# fejleszt.net
KiCad netlist of a schematic drawn in EAGLE
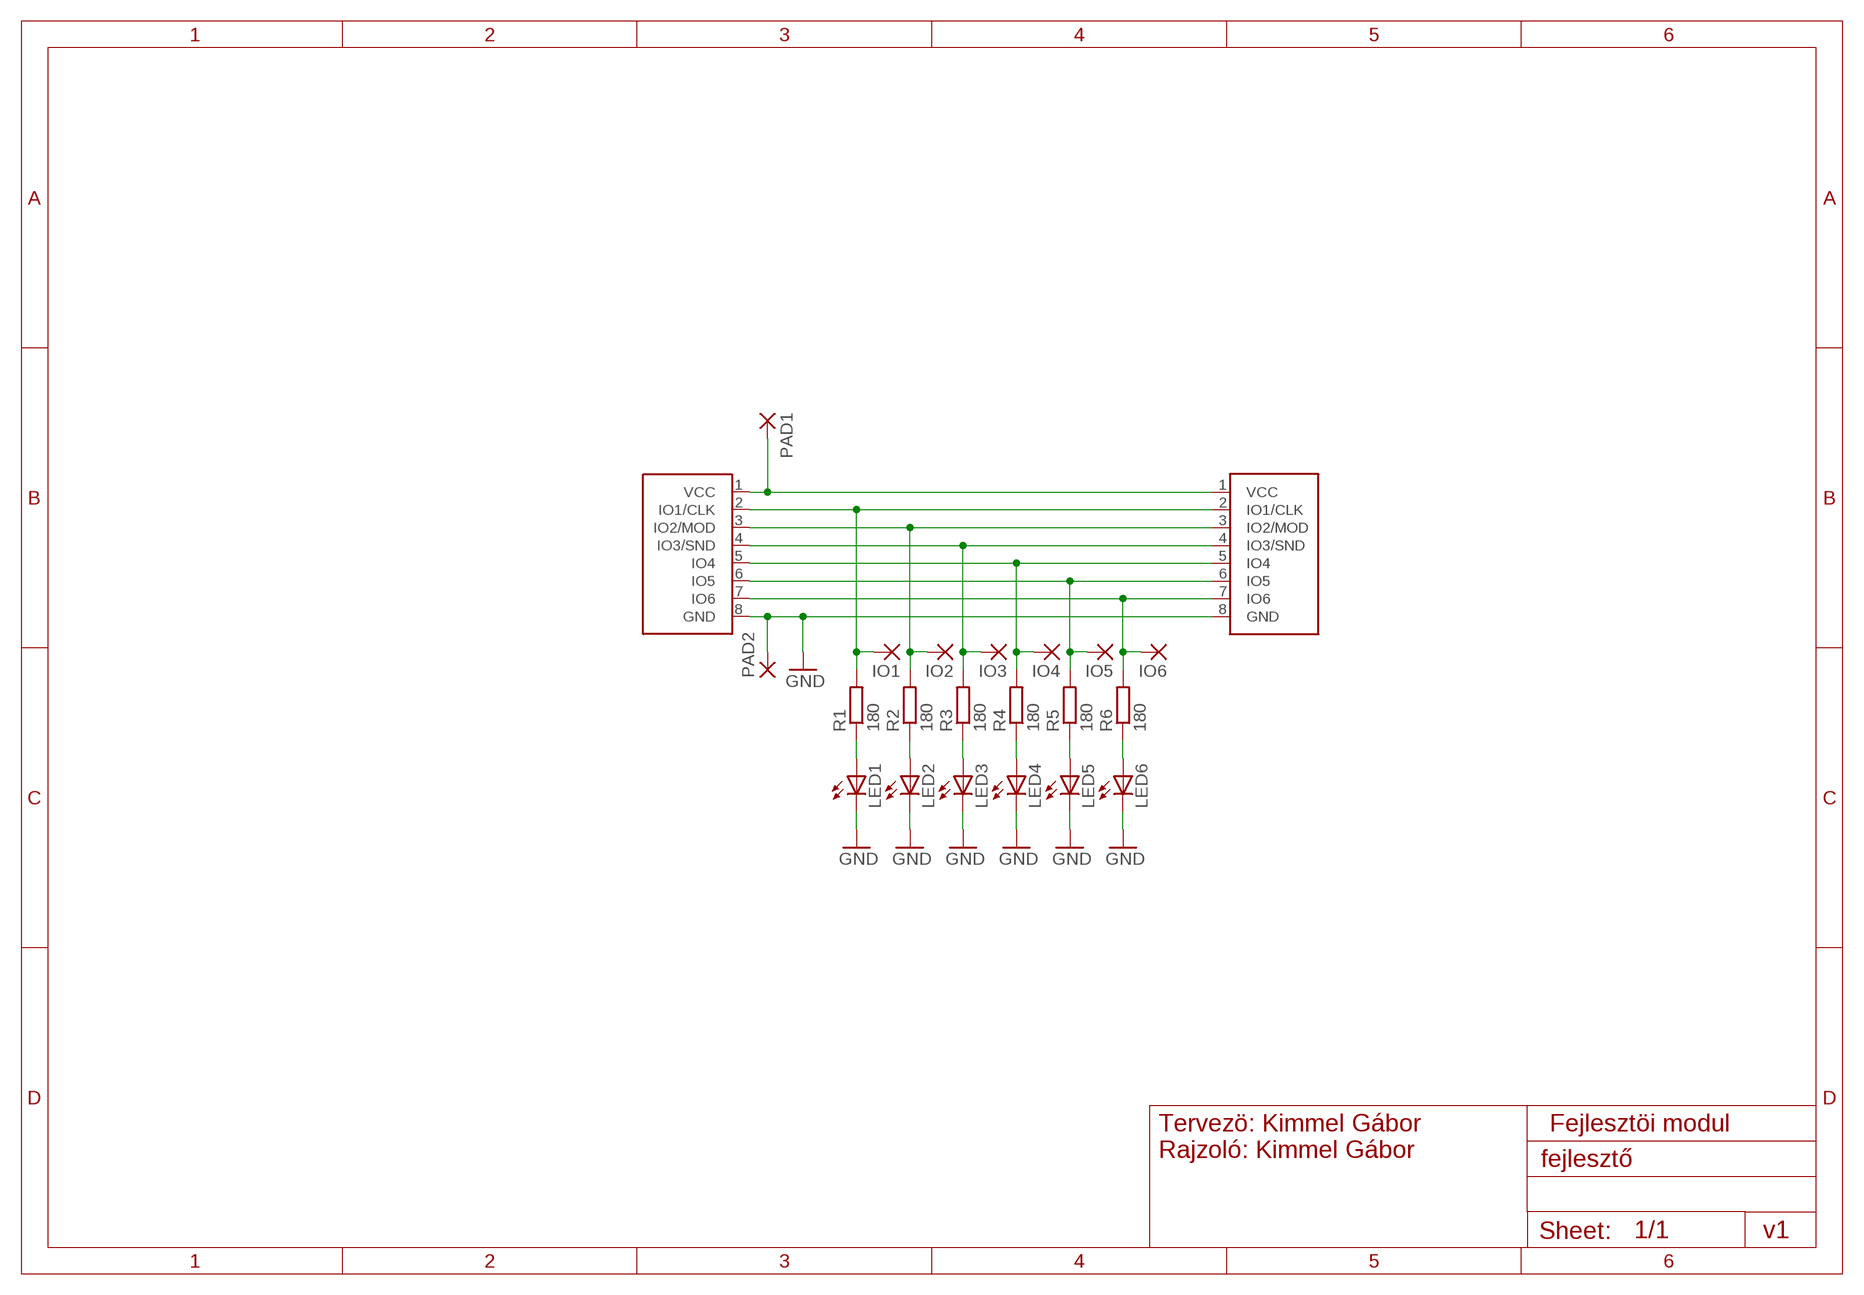
[diagram p0: schematic, sheet 1]

(export (version "E")
  (design (tool "Eeschema 10.0.6"))
  (components
    (comp (ref "IO1")
      (value "2,15/1,0")
      (footprint "eagle-import:2,15_1,0")
      (libsource (lib "eagle-import") (part "2,15/1,0"))
    )
    (comp (ref "IO2")
      (value "2,15/1,0")
      (footprint "eagle-import:2,15_1,0")
      (libsource (lib "eagle-import") (part "2,15/1,0"))
    )
    (comp (ref "IO3")
      (value "2,15/1,0")
      (footprint "eagle-import:2,15_1,0")
      (libsource (lib "eagle-import") (part "2,15/1,0"))
    )
    (comp (ref "IO4")
      (value "2,15/1,0")
      (footprint "eagle-import:2,15_1,0")
      (libsource (lib "eagle-import") (part "2,15/1,0"))
    )
    (comp (ref "IO5")
      (value "2,15/1,0")
      (footprint "eagle-import:2,15_1,0")
      (libsource (lib "eagle-import") (part "2,15/1,0"))
    )
    (comp (ref "IO6")
      (value "2,15/1,0")
      (footprint "eagle-import:2,15_1,0")
      (libsource (lib "eagle-import") (part "2,15/1,0"))
    )
    (comp (ref "LED1")
      (value "LED5MM")
      (footprint "eagle-import:LED5MM")
      (libsource (lib "eagle-import") (part "LED5MM"))
    )
    (comp (ref "LED2")
      (value "LED5MM")
      (footprint "eagle-import:LED5MM")
      (libsource (lib "eagle-import") (part "LED5MM"))
    )
    (comp (ref "LED3")
      (value "LED5MM")
      (footprint "eagle-import:LED5MM")
      (libsource (lib "eagle-import") (part "LED5MM"))
    )
    (comp (ref "LED4")
      (value "LED5MM")
      (footprint "eagle-import:LED5MM")
      (libsource (lib "eagle-import") (part "LED5MM"))
    )
    (comp (ref "LED5")
      (value "LED5MM")
      (footprint "eagle-import:LED5MM")
      (libsource (lib "eagle-import") (part "LED5MM"))
    )
    (comp (ref "LED6")
      (value "LED5MM")
      (footprint "eagle-import:LED5MM")
      (libsource (lib "eagle-import") (part "LED5MM"))
    )
    (comp (ref "PAD1")
      (value "3,17/1,1")
      (footprint "eagle-import:3,17_1,1")
      (libsource (lib "eagle-import") (part "3,17/1,1"))
    )
    (comp (ref "PAD2")
      (value "3,17/1,1")
      (footprint "eagle-import:3,17_1,1")
      (libsource (lib "eagle-import") (part "3,17/1,1"))
    )
    (comp (ref "R1")
      (value "180")
      (footprint "eagle-import:0207_10")
      (libsource (lib "eagle-import") (part "R-EU_0207/10"))
    )
    (comp (ref "R2")
      (value "180")
      (footprint "eagle-import:0207_10")
      (libsource (lib "eagle-import") (part "R-EU_0207/10"))
    )
    (comp (ref "R3")
      (value "180")
      (footprint "eagle-import:0207_10")
      (libsource (lib "eagle-import") (part "R-EU_0207/10"))
    )
    (comp (ref "R4")
      (value "180")
      (footprint "eagle-import:0207_10")
      (libsource (lib "eagle-import") (part "R-EU_0207/10"))
    )
    (comp (ref "R5")
      (value "180")
      (footprint "eagle-import:0207_10")
      (libsource (lib "eagle-import") (part "R-EU_0207/10"))
    )
    (comp (ref "R6")
      (value "180")
      (footprint "eagle-import:0207_10")
      (libsource (lib "eagle-import") (part "R-EU_0207/10"))
    )
    (comp (ref "U$1")
      (value "GANZ-CONNECTOR")
      (footprint "eagle-import:FE08W")
      (libsource (lib "eagle-import") (part "GANZ-CONNECTOR"))
    )
    (comp (ref "U$2")
      (value "GANZ-CONNECTOR-OUT")
      (footprint "eagle-import:MA08-1W")
      (libsource (lib "eagle-import") (part "GANZ-CONNECTOR-OUT"))
    )
  )
  (nets
    (net (code "1") (name "GND") (class "Default")
      (node (ref "LED1") (pin "K") (pinfunction "C_K") (pintype "passive"))
      (node (ref "LED2") (pin "K") (pinfunction "C_K") (pintype "passive"))
      (node (ref "LED3") (pin "K") (pinfunction "C_K") (pintype "passive"))
      (node (ref "LED4") (pin "K") (pinfunction "C_K") (pintype "passive"))
      (node (ref "LED5") (pin "K") (pinfunction "C_K") (pintype "passive"))
      (node (ref "LED6") (pin "K") (pinfunction "C_K") (pintype "passive"))
      (node (ref "PAD2") (pin "1") (pinfunction "P_1") (pintype "passive"))
      (node (ref "U$1") (pin "8") (pinfunction "GND_8") (pintype "bidirectional"))
      (node (ref "U$2") (pin "8") (pinfunction "GND_8") (pintype "bidirectional"))
    )
    (net (code "2") (name "Net-(IO1-P)") (class "Default")
      (node (ref "IO1") (pin "1") (pinfunction "P_1") (pintype "passive"))
      (node (ref "R1") (pin "2") (pinfunction "2_2") (pintype "passive"))
      (node (ref "U$1") (pin "2") (pinfunction "IO1/CLK_2") (pintype "bidirectional"))
      (node (ref "U$2") (pin "2") (pinfunction "IO1/CLK_2") (pintype "bidirectional"))
    )
    (net (code "3") (name "Net-(IO2-P)") (class "Default")
      (node (ref "IO2") (pin "1") (pinfunction "P_1") (pintype "passive"))
      (node (ref "R2") (pin "2") (pinfunction "2_2") (pintype "passive"))
      (node (ref "U$1") (pin "3") (pinfunction "IO2/MOD_3") (pintype "bidirectional"))
      (node (ref "U$2") (pin "3") (pinfunction "IO2/MOD_3") (pintype "bidirectional"))
    )
    (net (code "4") (name "Net-(IO3-P)") (class "Default")
      (node (ref "IO3") (pin "1") (pinfunction "P_1") (pintype "passive"))
      (node (ref "R3") (pin "2") (pinfunction "2_2") (pintype "passive"))
      (node (ref "U$1") (pin "4") (pinfunction "IO3/SND_4") (pintype "bidirectional"))
      (node (ref "U$2") (pin "4") (pinfunction "IO3/SND_4") (pintype "bidirectional"))
    )
    (net (code "5") (name "Net-(IO4-P)") (class "Default")
      (node (ref "IO4") (pin "1") (pinfunction "P_1") (pintype "passive"))
      (node (ref "R4") (pin "2") (pinfunction "2_2") (pintype "passive"))
      (node (ref "U$1") (pin "5") (pinfunction "IO4_5") (pintype "bidirectional"))
      (node (ref "U$2") (pin "5") (pinfunction "IO4_5") (pintype "bidirectional"))
    )
    (net (code "6") (name "Net-(IO5-P)") (class "Default")
      (node (ref "IO5") (pin "1") (pinfunction "P_1") (pintype "passive"))
      (node (ref "R5") (pin "2") (pinfunction "2_2") (pintype "passive"))
      (node (ref "U$1") (pin "6") (pinfunction "IO5_6") (pintype "bidirectional"))
      (node (ref "U$2") (pin "6") (pinfunction "IO5_6") (pintype "bidirectional"))
    )
    (net (code "7") (name "Net-(IO6-P)") (class "Default")
      (node (ref "IO6") (pin "1") (pinfunction "P_1") (pintype "passive"))
      (node (ref "R6") (pin "2") (pinfunction "2_2") (pintype "passive"))
      (node (ref "U$1") (pin "7") (pinfunction "IO6_7") (pintype "bidirectional"))
      (node (ref "U$2") (pin "7") (pinfunction "IO6_7") (pintype "bidirectional"))
    )
    (net (code "8") (name "Net-(LED1-PadA)") (class "Default")
      (node (ref "LED1") (pin "A") (pinfunction "A_A") (pintype "passive"))
      (node (ref "R1") (pin "1") (pinfunction "1_1") (pintype "passive"))
    )
    (net (code "9") (name "Net-(LED2-PadA)") (class "Default")
      (node (ref "LED2") (pin "A") (pinfunction "A_A") (pintype "passive"))
      (node (ref "R2") (pin "1") (pinfunction "1_1") (pintype "passive"))
    )
    (net (code "10") (name "Net-(LED3-PadA)") (class "Default")
      (node (ref "LED3") (pin "A") (pinfunction "A_A") (pintype "passive"))
      (node (ref "R3") (pin "1") (pinfunction "1_1") (pintype "passive"))
    )
    (net (code "11") (name "Net-(LED4-PadA)") (class "Default")
      (node (ref "LED4") (pin "A") (pinfunction "A_A") (pintype "passive"))
      (node (ref "R4") (pin "1") (pinfunction "1_1") (pintype "passive"))
    )
    (net (code "12") (name "Net-(LED5-PadA)") (class "Default")
      (node (ref "LED5") (pin "A") (pinfunction "A_A") (pintype "passive"))
      (node (ref "R5") (pin "1") (pinfunction "1_1") (pintype "passive"))
    )
    (net (code "13") (name "Net-(LED6-PadA)") (class "Default")
      (node (ref "LED6") (pin "A") (pinfunction "A_A") (pintype "passive"))
      (node (ref "R6") (pin "1") (pinfunction "1_1") (pintype "passive"))
    )
    (net (code "14") (name "Net-(PAD1-P)") (class "Default")
      (node (ref "PAD1") (pin "1") (pinfunction "P_1") (pintype "passive"))
      (node (ref "U$1") (pin "1") (pinfunction "VCC_1") (pintype "bidirectional"))
      (node (ref "U$2") (pin "1") (pinfunction "VCC_1") (pintype "bidirectional"))
    )
  )
)
